# PCB_ArduinoShield.net
KiCad netlist of a schematic drawn in EasyEDA
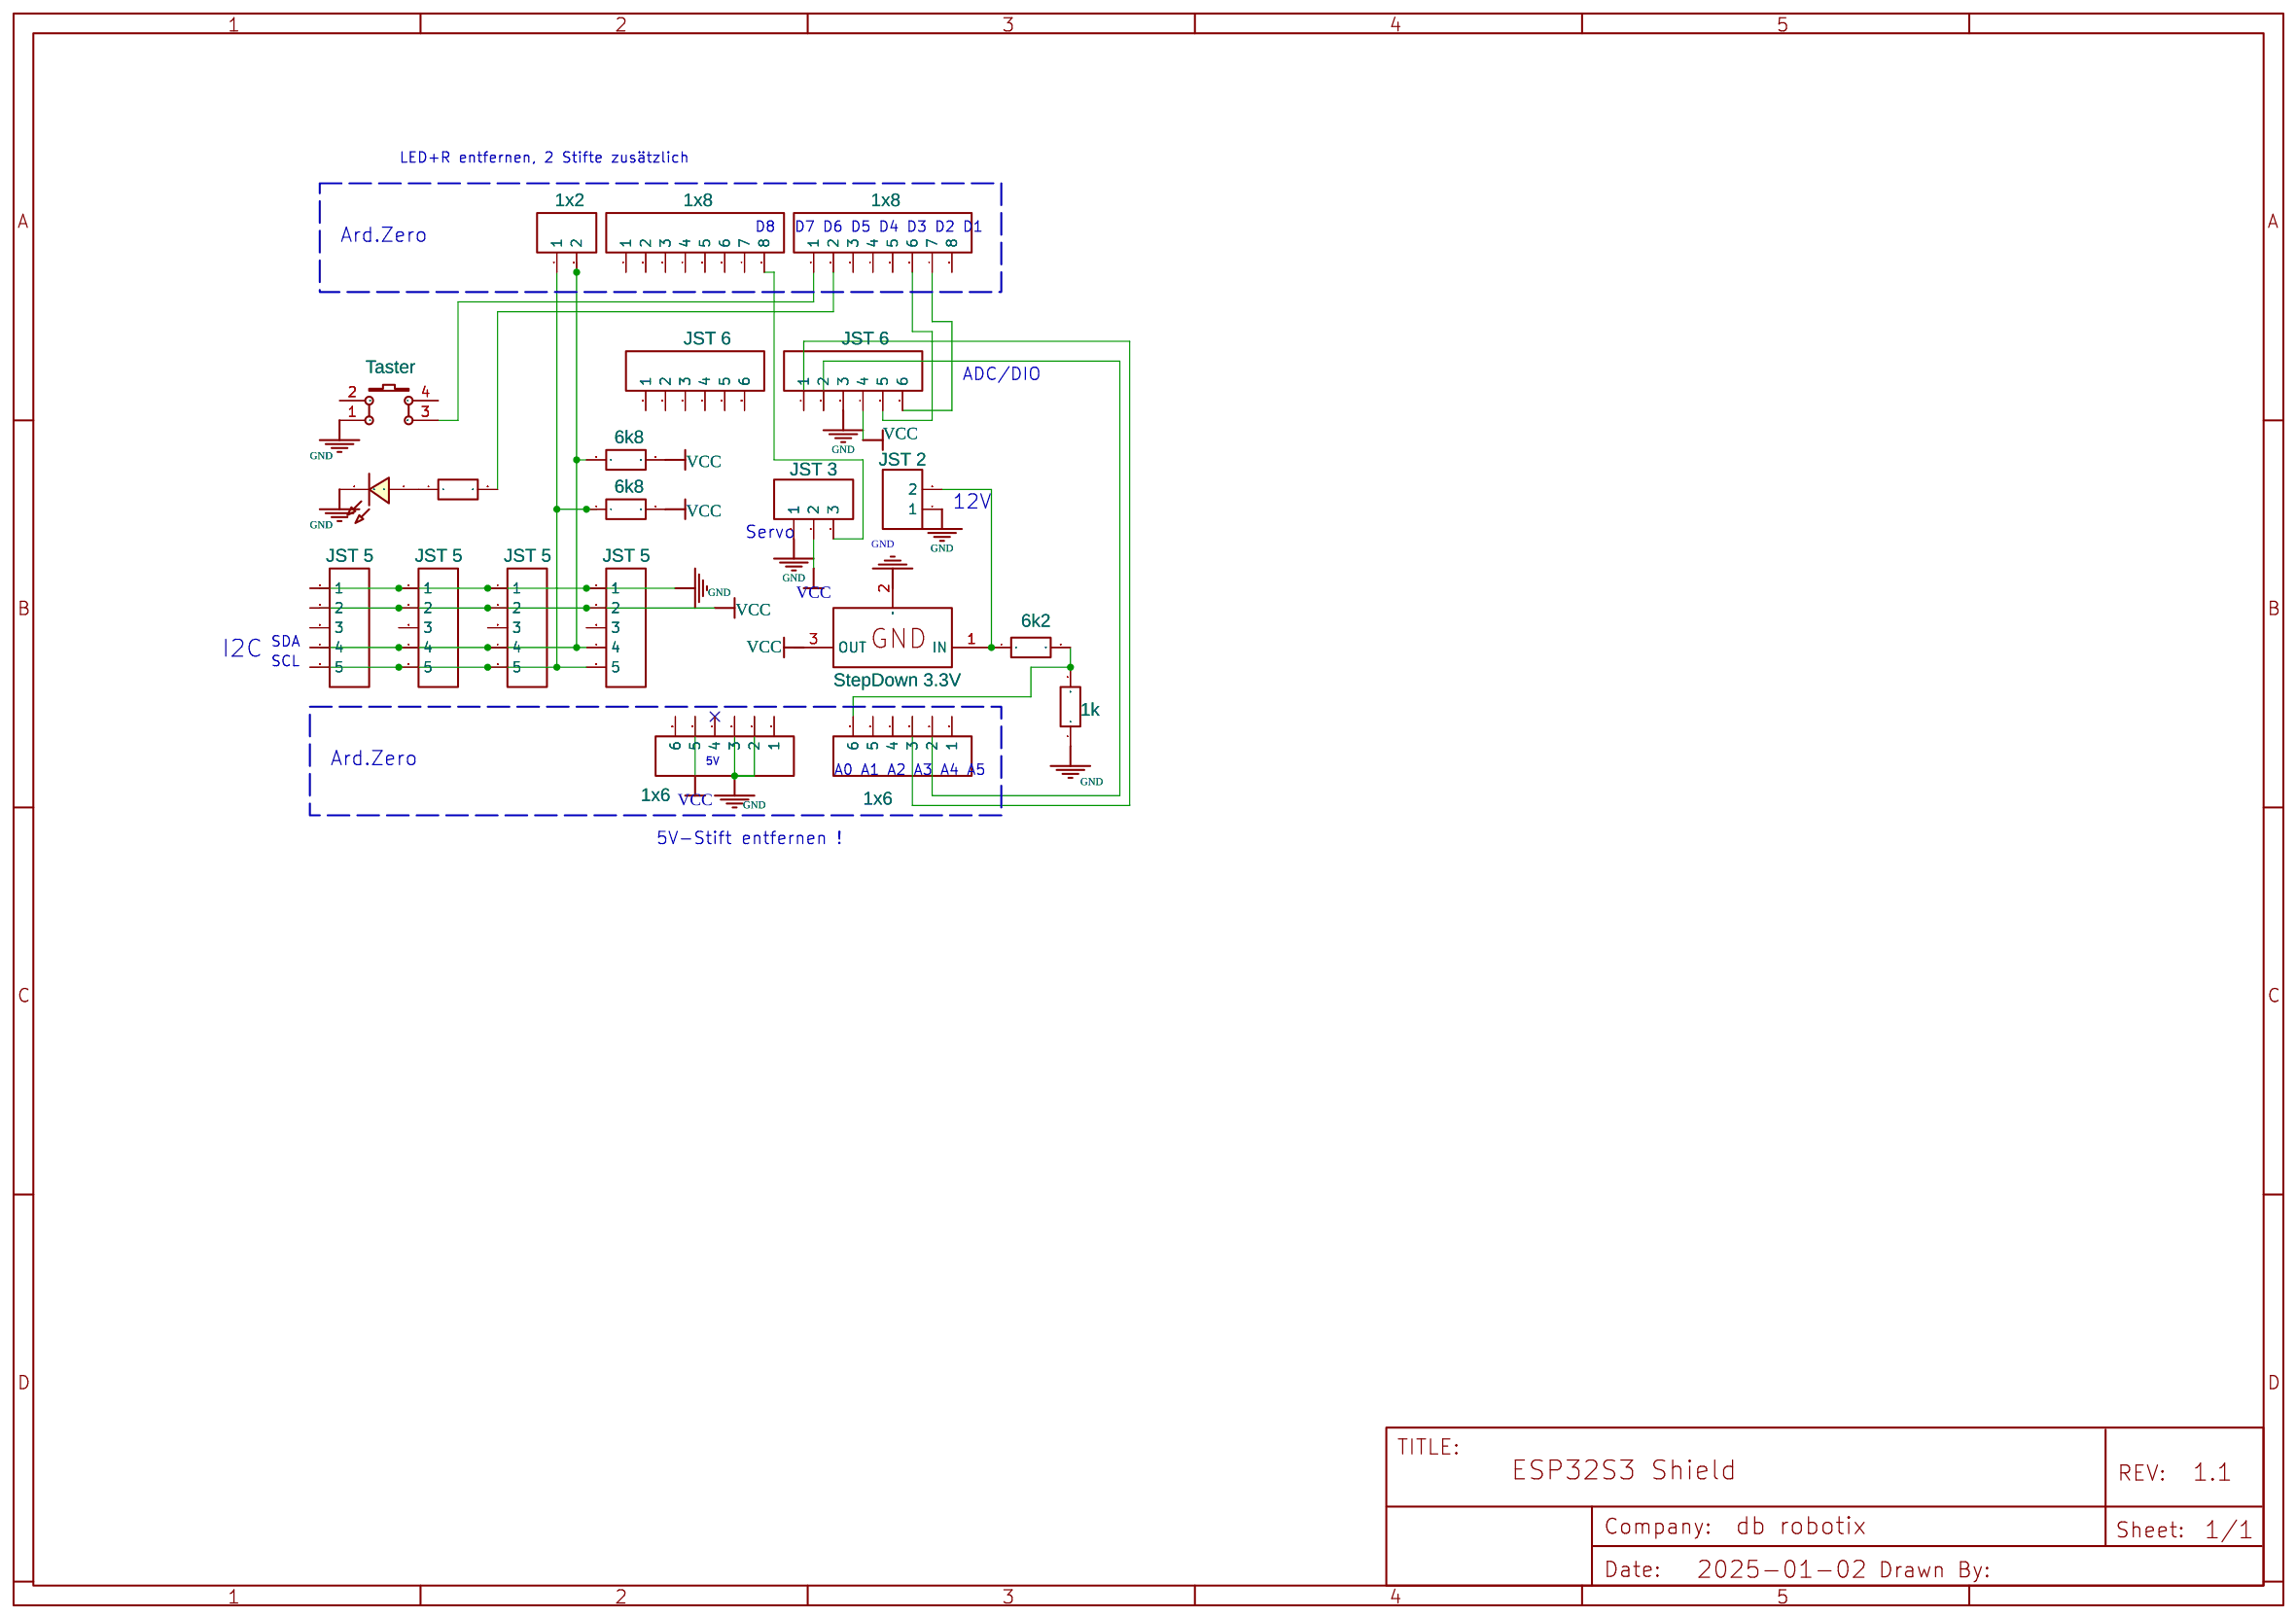
[diagram p0: schematic sheet]

(export (version "E")
  (design (tool "Eeschema 10.0.6"))
  (components
    (comp (ref "H1") (value "1x8") (libsource (lib "") (part "HDR-F-2.54_1x8")))
    (comp (ref "H2") (value "1x8") (libsource (lib "") (part "HDR-F-2.54_1x8")))
    (comp (ref "H3") (value "1x2") (libsource (lib "") (part "HDR-F-2.54_1x2")))
    (comp (ref "H4") (value "1x6") (libsource (lib "") (part "HDR-F-2.54_1x6")))
    (comp (ref "H5") (value "1x6") (libsource (lib "") (part "HDR-F-2.54_1x6")))
    (comp (ref "H6") (value "JST 6") (libsource (lib "") (part "HDR-F-2.54_1x6_1")))
    (comp (ref "H7") (value "JST 6") (libsource (lib "") (part "HDR-F-2.54_1x6_1")))
    (comp (ref "H8") (value "JST 3") (libsource (lib "") (part "HDR-F-2.54_1x3")))
    (comp (ref "H9") (value "JST 5") (libsource (lib "") (part "HDR-F-2.54_1x5")))
    (comp (ref "H10") (value "JST 5") (libsource (lib "") (part "HDR-F-2.54_1x5")))
    (comp (ref "H11") (value "JST 5") (libsource (lib "") (part "HDR-F-2.54_1x5")))
    (comp (ref "H12") (value "JST 5") (libsource (lib "") (part "HDR-F-2.54_1x5")))
    (comp (ref "H13") (value "JST 2") (libsource (lib "") (part "HDR-F-2.54_1x2_1")))
    (comp (ref "KEY1")
      (value "Taster")
      (fields (field (name "Manufacturer Part") "K2-1102DP-E4SW-04") (field (name "Manufacturer") "韩国韩荣"))
      (libsource (lib "") (part "K4-6×6_TH"))
    )
    (comp (ref "LED1")
      (value "LED-0603_R")
      (fields
        (field (name "Manufacturer Part") "19-217/R6C-AL1M2VY/3T")
        (field (name "Manufacturer") "EVERLIGHT(台湾亿光)")
      )
      (libsource (lib "") (part "LED-0603_R"))
    )
    (comp (ref "R1") (value "6k2") (libsource (lib "") (part "R_0603_EU")))
    (comp (ref "R2") (value "1k") (libsource (lib "") (part "R_0603_EU_1")))
    (comp (ref "R3") (value "1k") (libsource (lib "") (part "R_0603_EU")))
    (comp (ref "R4") (value "6k8") (libsource (lib "") (part "R_0603_EU")))
    (comp (ref "R5") (value "6k8") (libsource (lib "") (part "R_0603_EU")))
    (comp (ref "U1")
      (value "StepDown 3.3V")
      (fields
        (field (name "Manufacturer Part") "L7805CV-DG")
        (field (name "Manufacturer") "STMicroelectronics")
      )
      (libsource (lib "") (part "7805(TO-220)"))
    )
  )
  (nets
    (net (code "1") (name "GND") (class "Default")
      (node (ref "H10") (pin "1") (pinfunction "1_1") (pintype "unspecified"))
      (node (ref "H11") (pin "1") (pinfunction "1_1") (pintype "unspecified"))
      (node (ref "H12") (pin "1") (pinfunction "1_1") (pintype "unspecified"))
      (node (ref "H13") (pin "1") (pinfunction "1_1") (pintype "input"))
      (node (ref "H5") (pin "2") (pinfunction "2_2") (pintype "input"))
      (node (ref "H5") (pin "3") (pinfunction "3_3") (pintype "input"))
      (node (ref "H7") (pin "3") (pinfunction "3_3") (pintype "input"))
      (node (ref "H8") (pin "1") (pinfunction "1_1") (pintype "input"))
      (node (ref "KEY1") (pin "1") (pinfunction "1_1") (pintype "unspecified"))
      (node (ref "LED1") (pin "2") (pinfunction "2_2") (pintype "unspecified"))
      (node (ref "R2") (pin "1") (pinfunction "1_1") (pintype "unspecified"))
    )
    (net (code "2") (name "Net-(H1-Pad1)") (class "Default")
      (node (ref "H1") (pin "1") (pinfunction "1_1") (pintype "unspecified"))
      (node (ref "KEY1") (pin "3") (pinfunction "3_3") (pintype "unspecified"))
    )
    (net (code "3") (name "Net-(H1-Pad2)") (class "Default")
      (node (ref "H1") (pin "2") (pinfunction "2_2") (pintype "unspecified"))
      (node (ref "R3") (pin "2") (pinfunction "2_2") (pintype "unspecified"))
    )
    (net (code "4") (name "Net-(H1-Pad6)") (class "Default")
      (node (ref "H1") (pin "6") (pinfunction "6_6") (pintype "unspecified"))
      (node (ref "H7") (pin "5") (pinfunction "5_5") (pintype "input"))
    )
    (net (code "5") (name "Net-(H1-Pad7)") (class "Default")
      (node (ref "H1") (pin "7") (pinfunction "7_7") (pintype "unspecified"))
      (node (ref "H7") (pin "6") (pinfunction "6_6") (pintype "input"))
    )
    (net (code "6") (name "Net-(H2-Pad8)") (class "Default")
      (node (ref "H2") (pin "8") (pinfunction "8_8") (pintype "unspecified"))
      (node (ref "H8") (pin "3") (pinfunction "3_3") (pintype "input"))
    )
    (net (code "7") (name "Net-(H4-Pad2)") (class "Default")
      (node (ref "H4") (pin "2") (pinfunction "2_2") (pintype "input"))
      (node (ref "H7") (pin "2") (pinfunction "2_2") (pintype "input"))
    )
    (net (code "8") (name "Net-(H4-Pad3)") (class "Default")
      (node (ref "H4") (pin "3") (pinfunction "3_3") (pintype "input"))
      (node (ref "H7") (pin "1") (pinfunction "1_1") (pintype "input"))
    )
    (net (code "9") (name "Net-(H4-Pad6)") (class "Default")
      (node (ref "H4") (pin "6") (pinfunction "6_6") (pintype "input"))
      (node (ref "R1") (pin "2") (pinfunction "2_2") (pintype "unspecified"))
      (node (ref "R2") (pin "2") (pinfunction "2_2") (pintype "unspecified"))
    )
    (net (code "10") (name "Net-(H10-Pad4)") (class "Default")
      (node (ref "H10") (pin "4") (pinfunction "4_4") (pintype "unspecified"))
      (node (ref "H11") (pin "4") (pinfunction "4_4") (pintype "unspecified"))
      (node (ref "H12") (pin "4") (pinfunction "4_4") (pintype "unspecified"))
      (node (ref "H3") (pin "2") (pinfunction "2_2") (pintype "input"))
      (node (ref "R4") (pin "1") (pinfunction "1_1") (pintype "unspecified"))
    )
    (net (code "11") (name "Net-(H10-Pad5)") (class "Default")
      (node (ref "H10") (pin "5") (pinfunction "5_5") (pintype "unspecified"))
      (node (ref "H11") (pin "5") (pinfunction "5_5") (pintype "unspecified"))
      (node (ref "H12") (pin "5") (pinfunction "5_5") (pintype "unspecified"))
      (node (ref "H3") (pin "1") (pinfunction "1_1") (pintype "input"))
      (node (ref "R5") (pin "1") (pinfunction "1_1") (pintype "unspecified"))
    )
    (net (code "12") (name "Net-(LED1-Pad1)") (class "Default")
      (node (ref "LED1") (pin "1") (pinfunction "1_1") (pintype "unspecified"))
      (node (ref "R3") (pin "1") (pinfunction "1_1") (pintype "unspecified"))
    )
    (net (code "13") (name "Net-(U1-IN)") (class "Default")
      (node (ref "H13") (pin "2") (pinfunction "2_2") (pintype "input"))
      (node (ref "R1") (pin "1") (pinfunction "1_1") (pintype "unspecified"))
      (node (ref "U1") (pin "1") (pinfunction "IN_1") (pintype "passive"))
    )
    (net (code "14") (name "VCC") (class "Default")
      (node (ref "H10") (pin "2") (pinfunction "2_2") (pintype "unspecified"))
      (node (ref "H11") (pin "2") (pinfunction "2_2") (pintype "unspecified"))
      (node (ref "H12") (pin "2") (pinfunction "2_2") (pintype "unspecified"))
      (node (ref "H5") (pin "5") (pinfunction "5_5") (pintype "input"))
      (node (ref "H7") (pin "4") (pinfunction "4_4") (pintype "input"))
      (node (ref "H8") (pin "2") (pinfunction "2_2") (pintype "input"))
      (node (ref "R4") (pin "2") (pinfunction "2_2") (pintype "unspecified"))
      (node (ref "R5") (pin "2") (pinfunction "2_2") (pintype "unspecified"))
    )
    (net (code "15") (name "unconnected-(H1-Pad3)") (class "Default")
      (node (ref "H1") (pin "3") (pinfunction "3_3") (pintype "unspecified"))
    )
    (net (code "16") (name "unconnected-(H1-Pad4)") (class "Default")
      (node (ref "H1") (pin "4") (pinfunction "4_4") (pintype "unspecified"))
    )
    (net (code "17") (name "unconnected-(H1-Pad5)") (class "Default")
      (node (ref "H1") (pin "5") (pinfunction "5_5") (pintype "unspecified"))
    )
    (net (code "18") (name "unconnected-(H1-Pad8)") (class "Default")
      (node (ref "H1") (pin "8") (pinfunction "8_8") (pintype "unspecified"))
    )
    (net (code "19") (name "unconnected-(H2-Pad1)") (class "Default")
      (node (ref "H2") (pin "1") (pinfunction "1_1") (pintype "unspecified"))
    )
    (net (code "20") (name "unconnected-(H2-Pad2)") (class "Default")
      (node (ref "H2") (pin "2") (pinfunction "2_2") (pintype "unspecified"))
    )
    (net (code "21") (name "unconnected-(H2-Pad3)") (class "Default")
      (node (ref "H2") (pin "3") (pinfunction "3_3") (pintype "unspecified"))
    )
    (net (code "22") (name "unconnected-(H2-Pad4)") (class "Default")
      (node (ref "H2") (pin "4") (pinfunction "4_4") (pintype "unspecified"))
    )
    (net (code "23") (name "unconnected-(H2-Pad5)") (class "Default")
      (node (ref "H2") (pin "5") (pinfunction "5_5") (pintype "unspecified"))
    )
    (net (code "24") (name "unconnected-(H2-Pad6)") (class "Default")
      (node (ref "H2") (pin "6") (pinfunction "6_6") (pintype "unspecified"))
    )
    (net (code "25") (name "unconnected-(H2-Pad7)") (class "Default")
      (node (ref "H2") (pin "7") (pinfunction "7_7") (pintype "unspecified"))
    )
    (net (code "26") (name "unconnected-(H4-Pad1)") (class "Default")
      (node (ref "H4") (pin "1") (pinfunction "1_1") (pintype "input"))
    )
    (net (code "27") (name "unconnected-(H4-Pad4)") (class "Default")
      (node (ref "H4") (pin "4") (pinfunction "4_4") (pintype "input"))
    )
    (net (code "28") (name "unconnected-(H4-Pad5)") (class "Default")
      (node (ref "H4") (pin "5") (pinfunction "5_5") (pintype "input"))
    )
    (net (code "29") (name "unconnected-(H5-Pad1)") (class "Default")
      (node (ref "H5") (pin "1") (pinfunction "1_1") (pintype "input"))
    )
    (net (code "30") (name "unconnected-(H5-Pad4)") (class "Default")
      (node (ref "H5") (pin "4") (pinfunction "4_4") (pintype "input+no_connect"))
    )
    (net (code "31") (name "unconnected-(H5-Pad6)") (class "Default")
      (node (ref "H5") (pin "6") (pinfunction "6_6") (pintype "input"))
    )
    (net (code "32") (name "unconnected-(H6-Pad1)") (class "Default")
      (node (ref "H6") (pin "1") (pinfunction "1_1") (pintype "input"))
    )
    (net (code "33") (name "unconnected-(H6-Pad2)") (class "Default")
      (node (ref "H6") (pin "2") (pinfunction "2_2") (pintype "input"))
    )
    (net (code "34") (name "unconnected-(H6-Pad3)") (class "Default")
      (node (ref "H6") (pin "3") (pinfunction "3_3") (pintype "input"))
    )
    (net (code "35") (name "unconnected-(H6-Pad4)") (class "Default")
      (node (ref "H6") (pin "4") (pinfunction "4_4") (pintype "input"))
    )
    (net (code "36") (name "unconnected-(H6-Pad5)") (class "Default")
      (node (ref "H6") (pin "5") (pinfunction "5_5") (pintype "input"))
    )
    (net (code "37") (name "unconnected-(H6-Pad6)") (class "Default")
      (node (ref "H6") (pin "6") (pinfunction "6_6") (pintype "input"))
    )
    (net (code "38") (name "unconnected-(H9-Pad1)") (class "Default")
      (node (ref "H9") (pin "1") (pinfunction "1_1") (pintype "unspecified"))
    )
    (net (code "39") (name "unconnected-(H9-Pad2)") (class "Default")
      (node (ref "H9") (pin "2") (pinfunction "2_2") (pintype "unspecified"))
    )
    (net (code "40") (name "unconnected-(H9-Pad3)") (class "Default")
      (node (ref "H9") (pin "3") (pinfunction "3_3") (pintype "unspecified"))
    )
    (net (code "41") (name "unconnected-(H9-Pad4)") (class "Default")
      (node (ref "H9") (pin "4") (pinfunction "4_4") (pintype "unspecified"))
    )
    (net (code "42") (name "unconnected-(H9-Pad5)") (class "Default")
      (node (ref "H9") (pin "5") (pinfunction "5_5") (pintype "unspecified"))
    )
    (net (code "43") (name "unconnected-(H10-Pad3)") (class "Default")
      (node (ref "H10") (pin "3") (pinfunction "3_3") (pintype "unspecified"))
    )
    (net (code "44") (name "unconnected-(H11-Pad3)") (class "Default")
      (node (ref "H11") (pin "3") (pinfunction "3_3") (pintype "unspecified"))
    )
    (net (code "45") (name "unconnected-(H12-Pad3)") (class "Default")
      (node (ref "H12") (pin "3") (pinfunction "3_3") (pintype "unspecified"))
    )
    (net (code "46") (name "unconnected-(KEY1-Pad2)") (class "Default")
      (node (ref "KEY1") (pin "2") (pinfunction "2_2") (pintype "unspecified"))
    )
    (net (code "47") (name "unconnected-(KEY1-Pad4)") (class "Default")
      (node (ref "KEY1") (pin "4") (pinfunction "4_4") (pintype "unspecified"))
    )
    (net (code "48") (name "unconnected-(U1-GND-Pad2)") (class "Default")
      (node (ref "U1") (pin "2") (pinfunction "GND_2") (pintype "passive"))
    )
    (net (code "49") (name "unconnected-(U1-OUT-Pad3)") (class "Default")
      (node (ref "U1") (pin "3") (pinfunction "OUT_3") (pintype "passive"))
    )
  )
)
